# PickupBoard.net
KiCad netlist of a schematic drawn in EAGLE
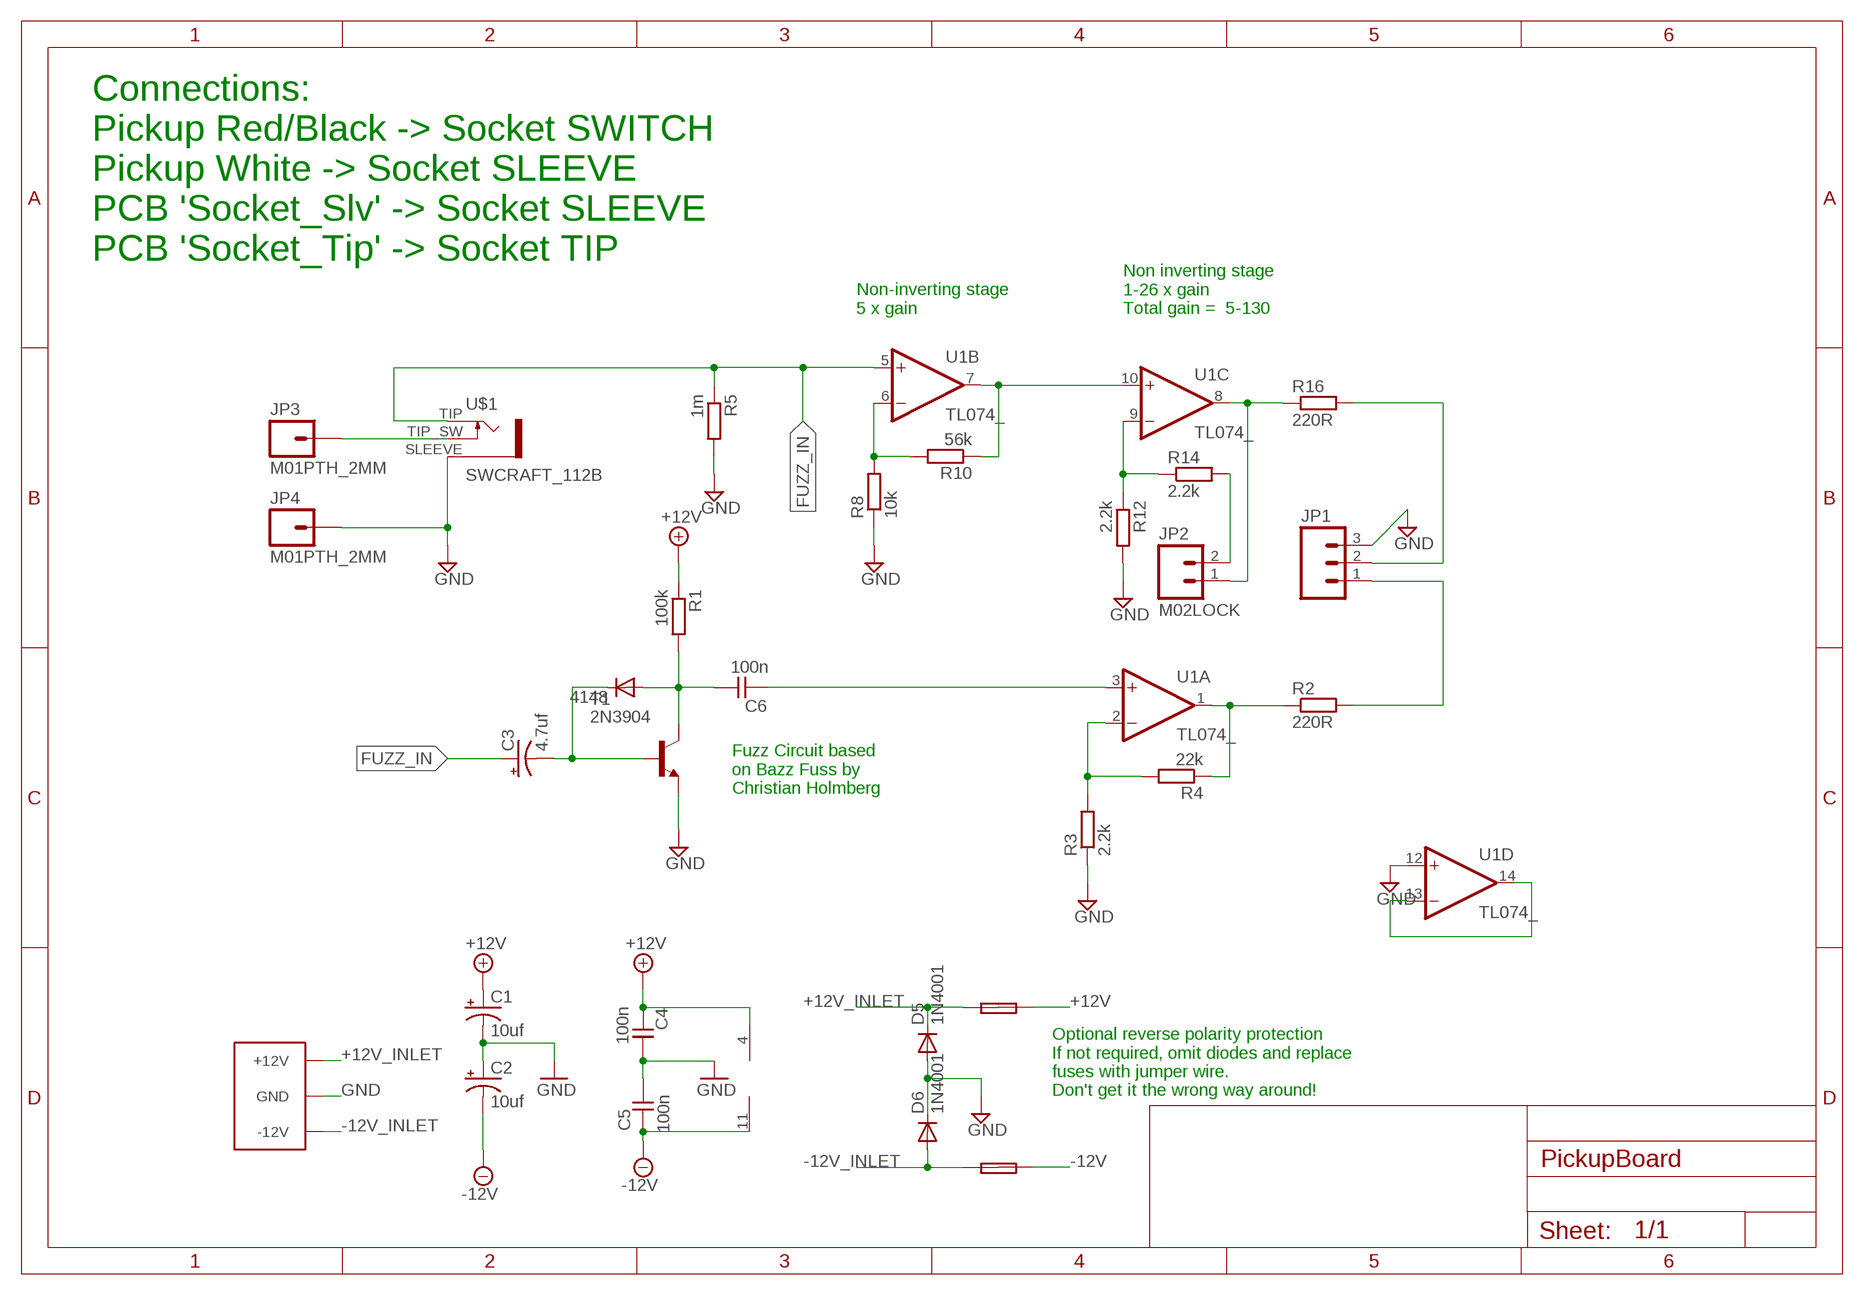
[diagram p0: schematic, sheet 1]

(export (version "E")
  (design (tool "Eeschema 10.0.6"))
  (components
    (comp (ref "1")
      (value "FUSE")
      (footprint "eagle-import:C050H075X075")
      (libsource (lib "eagle-import") (part "PTC_FUSEPOLY_FUSE"))
    )
    (comp (ref "4148")
      (value "SMALL_DIODEDO35-7")
      (footprint "eagle-import:DO35-7")
      (libsource (lib "eagle-import") (part "SMALL_DIODEDO35-7"))
    )
    (comp (ref "C1")
      (value "10uf")
      (footprint "eagle-import:CPOL-RADIAL-10UF-25V")
      (libsource (lib "eagle-import") (part "CAP_POLPTH2"))
    )
    (comp (ref "C2")
      (value "10uf")
      (footprint "eagle-import:CPOL-RADIAL-10UF-25V")
      (libsource (lib "eagle-import") (part "CAP_POLPTH2"))
    )
    (comp (ref "C3")
      (value "4.7uf")
      (footprint "eagle-import:CPOL-RADIAL-10UF-25V")
      (libsource (lib "eagle-import") (part "CAP_POLPTH2"))
    )
    (comp (ref "C4")
      (value "100n")
      (footprint "eagle-import:C050-024X044")
      (libsource (lib "eagle-import") (part "C-EU050-024X044"))
    )
    (comp (ref "C5")
      (value "100n")
      (footprint "eagle-import:C050-024X044")
      (libsource (lib "eagle-import") (part "C-EU050-024X044"))
    )
    (comp (ref "C6")
      (value "100n")
      (footprint "eagle-import:C050-024X044")
      (libsource (lib "eagle-import") (part "C-EU050-024X044"))
    )
    (comp (ref "D5")
      (value "1N4001")
      (footprint "eagle-import:DO41-10")
      (libsource (lib "eagle-import") (part "1N4004"))
    )
    (comp (ref "D6")
      (value "1N4001")
      (footprint "eagle-import:DO41-10")
      (libsource (lib "eagle-import") (part "1N4004"))
    )
    (comp (ref "FUSE")
      (value "FUSE")
      (footprint "eagle-import:C050H075X075")
      (libsource (lib "eagle-import") (part "PTC_FUSEPOLY_FUSE"))
    )
    (comp (ref "JP1")
      (value "M03LOCK")
      (footprint "eagle-import:1X03_LOCK")
      (libsource (lib "eagle-import") (part "M03LOCK"))
    )
    (comp (ref "JP2")
      (value "M02LOCK")
      (footprint "eagle-import:1X02_LOCK")
      (libsource (lib "eagle-import") (part "M02LOCK"))
    )
    (comp (ref "JP3")
      (value "M01PTH_2MM")
      (footprint "eagle-import:1X01_2MM")
      (libsource (lib "eagle-import") (part "M01PTH_2MM"))
    )
    (comp (ref "JP4")
      (value "M01PTH_2MM")
      (footprint "eagle-import:1X01_2MM")
      (libsource (lib "eagle-import") (part "M01PTH_2MM"))
    )
    (comp (ref "R1")
      (value "100k")
      (footprint "eagle-import:7MM_RESISTOR")
      (libsource (lib "eagle-import") (part "RESISTOR7MM"))
    )
    (comp (ref "R2")
      (value "220R")
      (footprint "eagle-import:7MM_RESISTOR")
      (libsource (lib "eagle-import") (part "RESISTOR7MM"))
    )
    (comp (ref "R3")
      (value "2.2k")
      (footprint "eagle-import:7MM_RESISTOR")
      (libsource (lib "eagle-import") (part "RESISTOR7MM"))
    )
    (comp (ref "R4")
      (value "22k")
      (footprint "eagle-import:7MM_RESISTOR")
      (libsource (lib "eagle-import") (part "RESISTOR7MM"))
    )
    (comp (ref "R5")
      (value "1m")
      (footprint "eagle-import:7MM_RESISTOR")
      (libsource (lib "eagle-import") (part "RESISTOR7MM"))
    )
    (comp (ref "R8")
      (value "10k")
      (footprint "eagle-import:7MM_RESISTOR")
      (libsource (lib "eagle-import") (part "RESISTOR7MM"))
    )
    (comp (ref "R10")
      (value "56k")
      (footprint "eagle-import:7MM_RESISTOR")
      (libsource (lib "eagle-import") (part "RESISTOR7MM"))
    )
    (comp (ref "R12")
      (value "2.2k")
      (footprint "eagle-import:7MM_RESISTOR")
      (libsource (lib "eagle-import") (part "RESISTOR7MM"))
    )
    (comp (ref "R14")
      (value "2.2k")
      (footprint "eagle-import:7MM_RESISTOR")
      (libsource (lib "eagle-import") (part "RESISTOR7MM"))
    )
    (comp (ref "R16")
      (value "220R")
      (footprint "eagle-import:7MM_RESISTOR")
      (libsource (lib "eagle-import") (part "RESISTOR7MM"))
    )
    (comp (ref "T1")
      (value "2N3904")
      (footprint "eagle-import:TO92")
      (libsource (lib "eagle-import") (part "2N3904"))
    )
    (comp (ref "U$1")
      (value "SWCRAFT_112B")
      (footprint "eagle-import:SWCRAFT_112_SLOTS")
      (libsource (lib "eagle-import") (part "SWCRAFT_112B"))
    )
    (comp (ref "U$2")
      (value "EURO_POWER_LOCK")
      (footprint "eagle-import:EURO_PWR_HEADER_LOCK")
      (libsource (lib "eagle-import") (part "EURO_POWER_LOCK"))
    )
    (comp (ref "U1")
      (value "TL074_")
      (footprint "eagle-import:DIL14")
      (libsource (lib "eagle-import") (part "TL074_"))
    )
  )
  (nets
    (net (code "1") (name "+12V") (class "Default")
      (node (ref "1") (pin "2") (pinfunction "P$2_2") (pintype "bidirectional"))
      (node (ref "C1") (pin "1") (pinfunction "+_1") (pintype "passive"))
      (node (ref "C4") (pin "2") (pinfunction "2_2") (pintype "passive"))
      (node (ref "R1") (pin "1") (pinfunction "1_1") (pintype "passive"))
      (node (ref "U1") (pin "4") (pinfunction "V+_4") (pintype "power_in"))
    )
    (net (code "2") (name "-12V") (class "Default")
      (node (ref "C2") (pin "2") (pinfunction "-_2") (pintype "passive"))
      (node (ref "C5") (pin "2") (pinfunction "2_2") (pintype "passive"))
      (node (ref "FUSE") (pin "2") (pinfunction "P$2_2") (pintype "bidirectional"))
      (node (ref "U1") (pin "11") (pinfunction "V-_11") (pintype "power_in"))
    )
    (net (code "3") (name "/+12V_INLET") (class "Default")
      (node (ref "1") (pin "1") (pinfunction "P$1_1") (pintype "bidirectional"))
      (node (ref "D5") (pin "C") (pinfunction "C_C") (pintype "passive"))
      (node (ref "U$2") (pin "POS1") (pinfunction "+12V_POS1") (pintype "bidirectional"))
      (node (ref "U$2") (pin "POS2") (pinfunction "+12V_POS2") (pintype "bidirectional"))
    )
    (net (code "4") (name "/-12V_INLET") (class "Default")
      (node (ref "D6") (pin "A") (pinfunction "A_A") (pintype "passive"))
      (node (ref "FUSE") (pin "1") (pinfunction "P$1_1") (pintype "bidirectional"))
      (node (ref "U$2") (pin "NEG1") (pinfunction "-12V_NEG1") (pintype "bidirectional"))
      (node (ref "U$2") (pin "NEG2") (pinfunction "-12V_NEG2") (pintype "bidirectional"))
    )
    (net (code "5") (name "FUZZ_IN") (class "Default")
      (node (ref "C3") (pin "1") (pinfunction "+_1") (pintype "passive"))
      (node (ref "R5") (pin "1") (pinfunction "1_1") (pintype "passive"))
      (node (ref "U$1") (pin "TIP") (pinfunction "3_TIP") (pintype "passive"))
      (node (ref "U1") (pin "5") (pinfunction "+IN_5") (pintype "input"))
    )
    (net (code "6") (name "GND") (class "Default")
      (node (ref "C1") (pin "2") (pinfunction "-_2") (pintype "passive"))
      (node (ref "C2") (pin "1") (pinfunction "+_1") (pintype "passive"))
      (node (ref "C4") (pin "1") (pinfunction "1_1") (pintype "passive"))
      (node (ref "C5") (pin "1") (pinfunction "1_1") (pintype "passive"))
      (node (ref "D5") (pin "A") (pinfunction "A_A") (pintype "passive"))
      (node (ref "D6") (pin "C") (pinfunction "C_C") (pintype "passive"))
      (node (ref "JP1") (pin "3") (pinfunction "3_3") (pintype "passive"))
      (node (ref "JP4") (pin "1") (pinfunction "1_1") (pintype "passive"))
      (node (ref "R12") (pin "2") (pinfunction "2_2") (pintype "passive"))
      (node (ref "R3") (pin "1") (pinfunction "1_1") (pintype "passive"))
      (node (ref "R5") (pin "2") (pinfunction "2_2") (pintype "passive"))
      (node (ref "R8") (pin "1") (pinfunction "1_1") (pintype "passive"))
      (node (ref "T1") (pin "3") (pinfunction "E_3") (pintype "passive"))
      (node (ref "U$1") (pin "SLEEVE") (pinfunction "5_SLEEVE") (pintype "passive"))
      (node (ref "U$2") (pin "GND1") (pinfunction "GND_GND1") (pintype "bidirectional"))
      (node (ref "U$2") (pin "GND2") (pinfunction "GND_GND2") (pintype "bidirectional"))
      (node (ref "U$2") (pin "GND3") (pinfunction "GND_GND3") (pintype "bidirectional"))
      (node (ref "U$2") (pin "GND4") (pinfunction "GND_GND4") (pintype "bidirectional"))
      (node (ref "U$2") (pin "GND5") (pinfunction "GND_GND5") (pintype "bidirectional"))
      (node (ref "U$2") (pin "GND6") (pinfunction "GND_GND6") (pintype "bidirectional"))
      (node (ref "U1") (pin "12") (pinfunction "+IN_12") (pintype "input"))
    )
    (net (code "7") (name "Net-(C3--)") (class "Default")
      (node (ref "4148") (pin "C") (pinfunction "C_C") (pintype "passive"))
      (node (ref "C3") (pin "2") (pinfunction "-_2") (pintype "passive"))
      (node (ref "T1") (pin "2") (pinfunction "B_2") (pintype "passive"))
    )
    (net (code "8") (name "Net-(JP1-Pad1)") (class "Default")
      (node (ref "JP1") (pin "1") (pinfunction "1_1") (pintype "passive"))
      (node (ref "R2") (pin "2") (pinfunction "2_2") (pintype "passive"))
    )
    (net (code "9") (name "Net-(JP1-Pad2)") (class "Default")
      (node (ref "JP1") (pin "2") (pinfunction "2_2") (pintype "passive"))
      (node (ref "R16") (pin "2") (pinfunction "2_2") (pintype "passive"))
    )
    (net (code "10") (name "Net-(JP2-Pad2)") (class "Default")
      (node (ref "JP2") (pin "2") (pinfunction "2_2") (pintype "passive"))
      (node (ref "R14") (pin "2") (pinfunction "2_2") (pintype "passive"))
    )
    (net (code "11") (name "Net-(T1-C)") (class "Default")
      (node (ref "4148") (pin "A") (pinfunction "A_A") (pintype "passive"))
      (node (ref "C6") (pin "1") (pinfunction "1_1") (pintype "passive"))
      (node (ref "R1") (pin "2") (pinfunction "2_2") (pintype "passive"))
      (node (ref "T1") (pin "1") (pinfunction "C_1") (pintype "passive"))
    )
    (net (code "12") (name "Net-(U$1-4)") (class "Default")
      (node (ref "JP3") (pin "1") (pinfunction "1_1") (pintype "passive"))
      (node (ref "U$1") (pin "TIP_SW") (pinfunction "4_TIP_SW") (pintype "passive"))
    )
    (net (code "13") (name "Net-(U1A-+IN)") (class "Default")
      (node (ref "C6") (pin "2") (pinfunction "2_2") (pintype "passive"))
      (node (ref "U1") (pin "3") (pinfunction "+IN_3") (pintype "input"))
    )
    (net (code "14") (name "Net-(U1A--IN)") (class "Default")
      (node (ref "R3") (pin "2") (pinfunction "2_2") (pintype "passive"))
      (node (ref "R4") (pin "2") (pinfunction "2_2") (pintype "passive"))
      (node (ref "U1") (pin "2") (pinfunction "-IN_2") (pintype "input"))
    )
    (net (code "15") (name "Net-(U1A-OUT)") (class "Default")
      (node (ref "R2") (pin "1") (pinfunction "1_1") (pintype "passive"))
      (node (ref "R4") (pin "1") (pinfunction "1_1") (pintype "passive"))
      (node (ref "U1") (pin "1") (pinfunction "OUT_1") (pintype "output"))
    )
    (net (code "16") (name "Net-(U1B--IN)") (class "Default")
      (node (ref "R10") (pin "2") (pinfunction "2_2") (pintype "passive"))
      (node (ref "R8") (pin "2") (pinfunction "2_2") (pintype "passive"))
      (node (ref "U1") (pin "6") (pinfunction "-IN_6") (pintype "input"))
    )
    (net (code "17") (name "Net-(U1B-OUT)") (class "Default")
      (node (ref "R10") (pin "1") (pinfunction "1_1") (pintype "passive"))
      (node (ref "U1") (pin "10") (pinfunction "+IN_10") (pintype "input"))
      (node (ref "U1") (pin "7") (pinfunction "OUT_7") (pintype "output"))
    )
    (net (code "18") (name "Net-(U1C--IN)") (class "Default")
      (node (ref "R12") (pin "1") (pinfunction "1_1") (pintype "passive"))
      (node (ref "R14") (pin "1") (pinfunction "1_1") (pintype "passive"))
      (node (ref "U1") (pin "9") (pinfunction "-IN_9") (pintype "input"))
    )
    (net (code "19") (name "Net-(U1C-OUT)") (class "Default")
      (node (ref "JP2") (pin "1") (pinfunction "1_1") (pintype "passive"))
      (node (ref "R16") (pin "1") (pinfunction "1_1") (pintype "passive"))
      (node (ref "U1") (pin "8") (pinfunction "OUT_8") (pintype "output"))
    )
    (net (code "20") (name "Net-(U1D--IN)") (class "Default")
      (node (ref "U1") (pin "13") (pinfunction "-IN_13") (pintype "input"))
      (node (ref "U1") (pin "14") (pinfunction "OUT_14") (pintype "output"))
    )
  )
)
